# n64cart.net
KiCad netlist of a schematic drawn in EAGLE
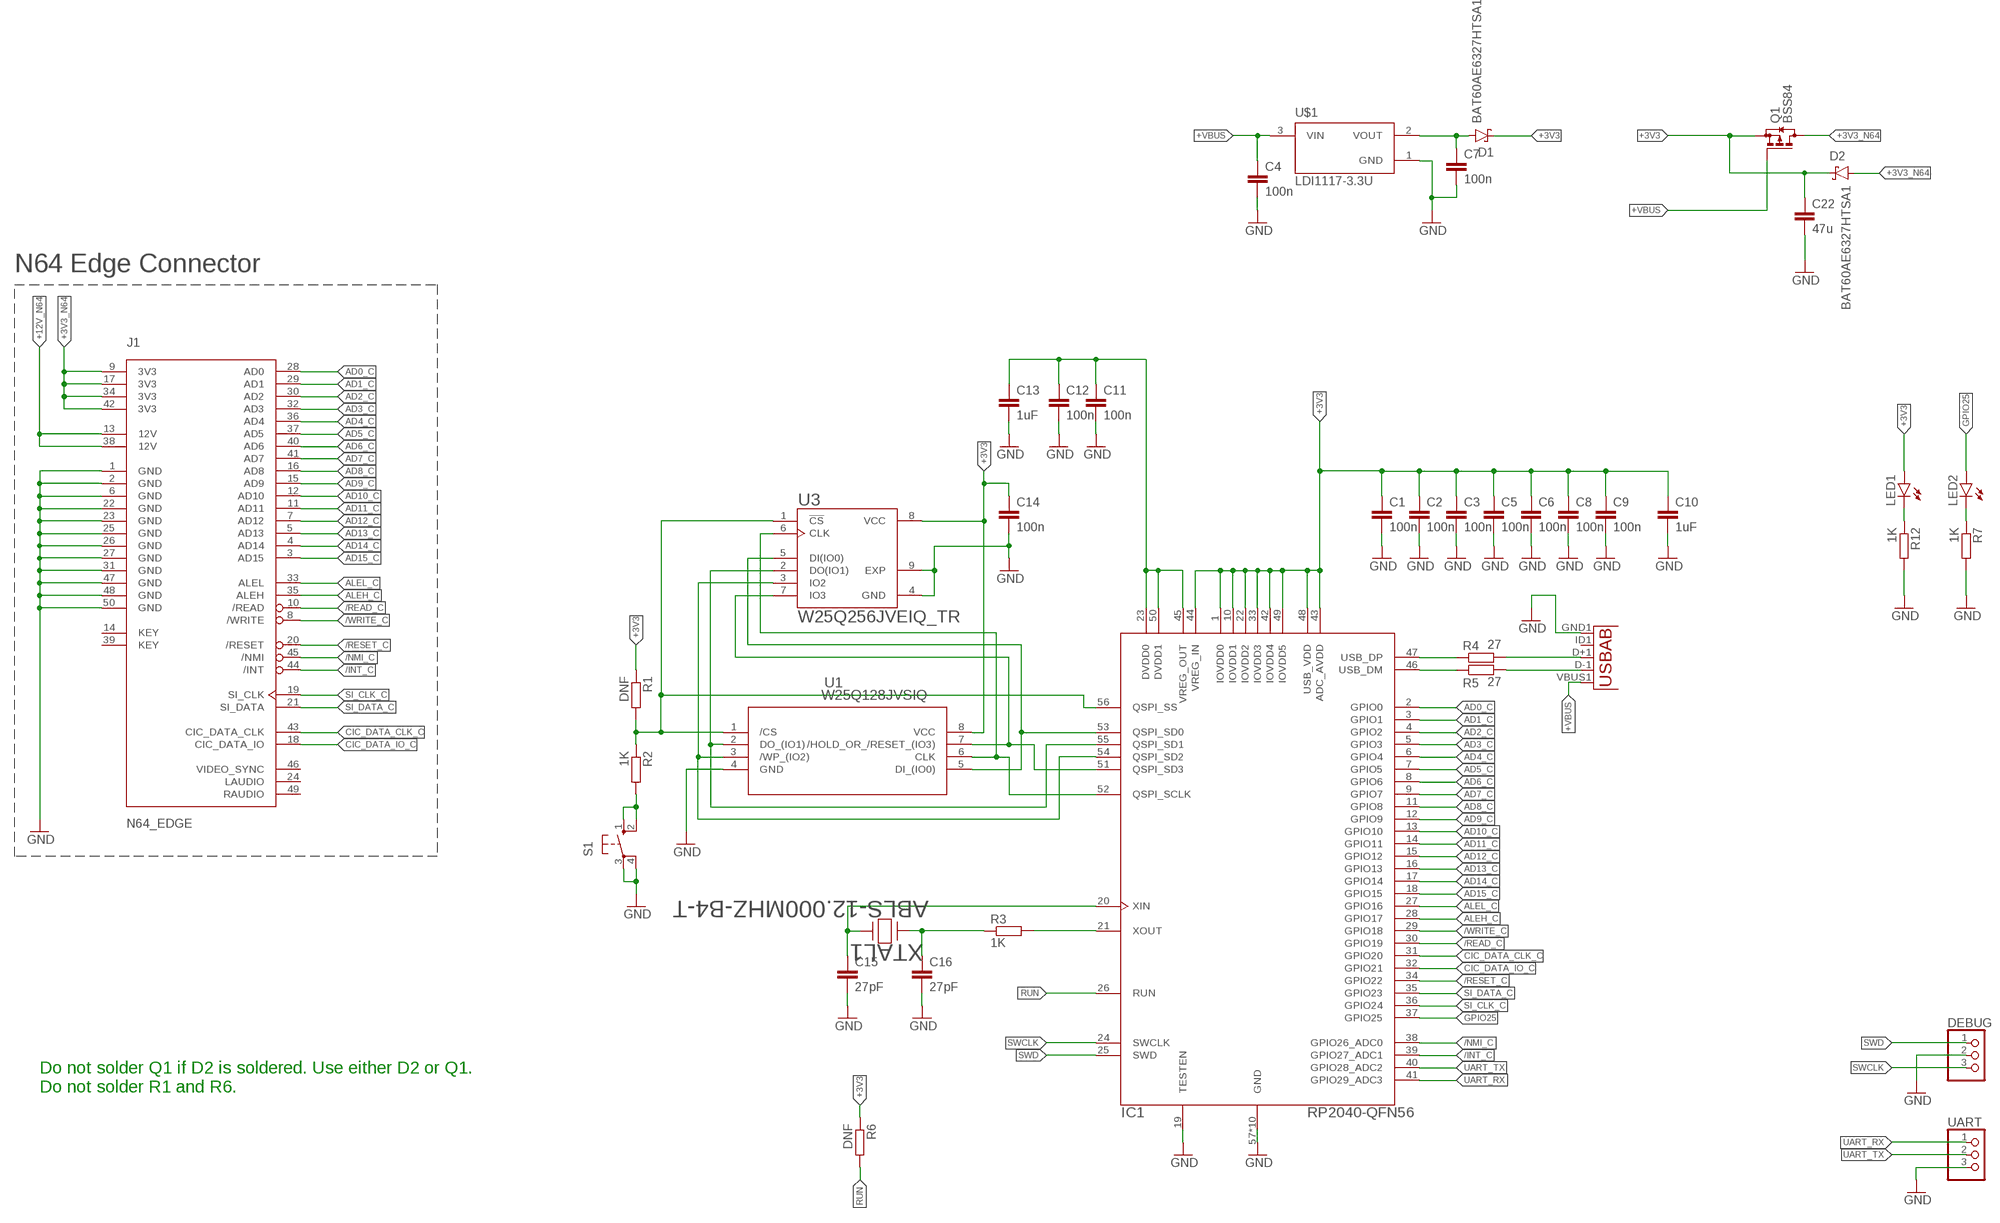
[diagram p0: schematic, sheet 1]

(export (version "E")
  (design (tool "Eeschema 10.0.6"))
  (components
    (comp (ref "C1")
      (value "100n")
      (footprint "eagle-import:C0402")
      (libsource (lib "eagle-import") (part "C-EUC0402"))
    )
    (comp (ref "C2")
      (value "100n")
      (footprint "eagle-import:C0402")
      (libsource (lib "eagle-import") (part "C-EUC0402"))
    )
    (comp (ref "C3")
      (value "100n")
      (footprint "eagle-import:C0402")
      (libsource (lib "eagle-import") (part "C-EUC0402"))
    )
    (comp (ref "C4")
      (value "100n")
      (footprint "eagle-import:C0402")
      (libsource (lib "eagle-import") (part "C-EUC0402"))
    )
    (comp (ref "C5")
      (value "100n")
      (footprint "eagle-import:C0402")
      (libsource (lib "eagle-import") (part "C-EUC0402"))
    )
    (comp (ref "C6")
      (value "100n")
      (footprint "eagle-import:C0402")
      (libsource (lib "eagle-import") (part "C-EUC0402"))
    )
    (comp (ref "C7")
      (value "100n")
      (footprint "eagle-import:C0402")
      (libsource (lib "eagle-import") (part "C-EUC0402"))
    )
    (comp (ref "C8")
      (value "100n")
      (footprint "eagle-import:C0402")
      (libsource (lib "eagle-import") (part "C-EUC0402"))
    )
    (comp (ref "C9")
      (value "100n")
      (footprint "eagle-import:C0402")
      (libsource (lib "eagle-import") (part "C-EUC0402"))
    )
    (comp (ref "C10")
      (value "1uF")
      (footprint "eagle-import:C0402")
      (libsource (lib "eagle-import") (part "C-EUC0402"))
    )
    (comp (ref "C11")
      (value "100n")
      (footprint "eagle-import:C0402")
      (libsource (lib "eagle-import") (part "C-EUC0402"))
    )
    (comp (ref "C12")
      (value "100n")
      (footprint "eagle-import:C0402")
      (libsource (lib "eagle-import") (part "C-EUC0402"))
    )
    (comp (ref "C13")
      (value "1uF")
      (footprint "eagle-import:C0402")
      (libsource (lib "eagle-import") (part "C-EUC0402"))
    )
    (comp (ref "C14")
      (value "100n")
      (footprint "eagle-import:C0402")
      (libsource (lib "eagle-import") (part "C-EUC0402"))
    )
    (comp (ref "C15")
      (value "27pF")
      (footprint "eagle-import:C0402")
      (libsource (lib "eagle-import") (part "C-EUC0402"))
    )
    (comp (ref "C16")
      (value "27pF")
      (footprint "eagle-import:C0402")
      (libsource (lib "eagle-import") (part "C-EUC0402"))
    )
    (comp (ref "C22")
      (value "47u")
      (footprint "eagle-import:C0805")
      (libsource (lib "eagle-import") (part "C-EUC0805"))
    )
    (comp (ref "D1")
      (value "BAT60AE6327HTSA1")
      (footprint "eagle-import:SOD323_ST")
      (libsource (lib "eagle-import") (part "BAT60J"))
    )
    (comp (ref "D2")
      (value "BAT60AE6327HTSA1")
      (footprint "eagle-import:SOD323_ST")
      (libsource (lib "eagle-import") (part "BAT60J"))
    )
    (comp (ref "DEBUG")
      (value "PINHD-1X3")
      (footprint "eagle-import:1X03")
      (libsource (lib "eagle-import") (part "PINHD-1X3"))
    )
    (comp (ref "IC1")
      (value "RP2040-QFN56")
      (footprint "eagle-import:RP2040-QFN-56")
      (libsource (lib "eagle-import") (part "RP2040-QFN56"))
    )
    (comp (ref "J1")
      (value "N64_EDGE")
      (footprint "eagle-import:N64_EDGE")
      (libsource (lib "eagle-import") (part "N64_EDGE"))
    )
    (comp (ref "LED1")
      (value "LED5MM")
      (footprint "eagle-import:LED5MM")
      (libsource (lib "eagle-import") (part "LED5MM"))
    )
    (comp (ref "LED2")
      (value "LED5MM")
      (footprint "eagle-import:LED5MM")
      (libsource (lib "eagle-import") (part "LED5MM"))
    )
    (comp (ref "Q1")
      (value "BSS84")
      (footprint "eagle-import:SOT23")
      (libsource (lib "eagle-import") (part "BSS84"))
    )
    (comp (ref "R1")
      (value "DNF")
      (footprint "eagle-import:R0402")
      (libsource (lib "eagle-import") (part "R-EU_R0402"))
    )
    (comp (ref "R2")
      (value "1K")
      (footprint "eagle-import:R0402")
      (libsource (lib "eagle-import") (part "R-EU_R0402"))
    )
    (comp (ref "R3")
      (value "1K")
      (footprint "eagle-import:R0402")
      (libsource (lib "eagle-import") (part "R-EU_R0402"))
    )
    (comp (ref "R4")
      (value "27")
      (footprint "eagle-import:R0402")
      (libsource (lib "eagle-import") (part "R-EU_R0402"))
    )
    (comp (ref "R5")
      (value "27")
      (footprint "eagle-import:R0402")
      (libsource (lib "eagle-import") (part "R-EU_R0402"))
    )
    (comp (ref "R6")
      (value "DNF")
      (footprint "eagle-import:R0402")
      (libsource (lib "eagle-import") (part "R-EU_R0402"))
    )
    (comp (ref "R7")
      (value "1K")
      (footprint "eagle-import:R0402")
      (libsource (lib "eagle-import") (part "R-EU_R0402"))
    )
    (comp (ref "R12")
      (value "1K")
      (footprint "eagle-import:R0402")
      (libsource (lib "eagle-import") (part "R-EU_R0402"))
    )
    (comp (ref "S1")
      (value "10-XX")
      (footprint "eagle-import:B3F-10XX")
      (fields (field (name "MPN") "B3F-1000"))
      (libsource (lib "eagle-import") (part "10-XX"))
    )
    (comp (ref "U$1")
      (value "LDI1117-3.3U")
      (footprint "eagle-import:LDI1117-3.3U")
      (libsource (lib "eagle-import") (part "LDI1117-3.3U"))
    )
    (comp (ref "U1")
      (value "W25Q128JVSIQ")
      (footprint "eagle-import:SOIC_128JVSIQ_WIN")
      (fields (field (name "COPYRIGHT") "Copyright (C) 2022 Ultra Librarian. All rights reserved."))
      (libsource (lib "eagle-import") (part "W25Q128JVSIQ"))
    )
    (comp (ref "U2")
      (value "USB\"\"")
      (footprint "eagle-import:USB-MICRO-SMD")
      (libsource (lib "eagle-import") (part "USB{dblquote}{dblquote}"))
    )
    (comp (ref "U3")
      (value "W25Q256JVEIQ_TR")
      (footprint "eagle-import:SON127P800X600X80-9N")
      (fields
        (field (name "DIGI-KEY_PART_NUMBER") "W25Q256JVEIQTR-ND")
        (field (name "MF") "Winbond")
        (field (name "MP") "W25Q256JVEIQ TR")
      )
      (libsource (lib "eagle-import") (part "W25Q256JVEIQ_TR"))
    )
    (comp (ref "UART")
      (value "PINHD-1X3")
      (footprint "eagle-import:1X03")
      (libsource (lib "eagle-import") (part "PINHD-1X3"))
    )
    (comp (ref "XTAL1")
      (value "ABLS-12.000MHZ-B4-T")
      (footprint "eagle-import:XTAL_ABLS_ABR")
      (fields (field (name "COPYRIGHT") "Copyright (C) 2022 Ultra Librarian. All rights reserved."))
      (libsource (lib "eagle-import") (part "ABLS-12.000MHZ-B4-T"))
    )
  )
  (nets
    (net (code "1") (name "+3V3") (class "Default")
      (node (ref "C1") (pin "1") (pinfunction "1_1") (pintype "passive"))
      (node (ref "C10") (pin "1") (pinfunction "1_1") (pintype "passive"))
      (node (ref "C14") (pin "1") (pinfunction "1_1") (pintype "passive"))
      (node (ref "C2") (pin "1") (pinfunction "1_1") (pintype "passive"))
      (node (ref "C22") (pin "1") (pinfunction "1_1") (pintype "passive"))
      (node (ref "C3") (pin "1") (pinfunction "1_1") (pintype "passive"))
      (node (ref "C5") (pin "1") (pinfunction "1_1") (pintype "passive"))
      (node (ref "C6") (pin "1") (pinfunction "1_1") (pintype "passive"))
      (node (ref "C8") (pin "1") (pinfunction "1_1") (pintype "passive"))
      (node (ref "C9") (pin "1") (pinfunction "1_1") (pintype "passive"))
      (node (ref "D1") (pin "C") (pinfunction "C_C") (pintype "passive"))
      (node (ref "D2") (pin "C") (pinfunction "C_C") (pintype "passive"))
      (node (ref "IC1") (pin "1") (pinfunction "IOVDD0_1") (pintype "power_in"))
      (node (ref "IC1") (pin "10") (pinfunction "IOVDD1_10") (pintype "power_in"))
      (node (ref "IC1") (pin "22") (pinfunction "IOVDD2_22") (pintype "power_in"))
      (node (ref "IC1") (pin "33") (pinfunction "IOVDD3_33") (pintype "power_in"))
      (node (ref "IC1") (pin "42") (pinfunction "IOVDD4_42") (pintype "power_in"))
      (node (ref "IC1") (pin "43") (pinfunction "ADC_AVDD_43") (pintype "power_in"))
      (node (ref "IC1") (pin "44") (pinfunction "VREG_IN_44") (pintype "power_in"))
      (node (ref "IC1") (pin "48") (pinfunction "USB_VDD_48") (pintype "power_in"))
      (node (ref "IC1") (pin "49") (pinfunction "IOVDD5_49") (pintype "power_in"))
      (node (ref "LED1") (pin "A") (pinfunction "A_A") (pintype "passive"))
      (node (ref "Q1") (pin "2") (pinfunction "S_2") (pintype "passive"))
      (node (ref "R1") (pin "1") (pinfunction "1_1") (pintype "passive"))
      (node (ref "R6") (pin "1") (pinfunction "1_1") (pintype "passive"))
      (node (ref "U1") (pin "8") (pinfunction "VCC_8") (pintype "power_in"))
      (node (ref "U3") (pin "8") (pinfunction "VCC_8") (pintype "power_in"))
    )
    (net (code "2") (name "+3V3_N64") (class "Default")
      (node (ref "D2") (pin "A") (pinfunction "A_A") (pintype "passive"))
      (node (ref "J1") (pin "17") (pinfunction "3V3_17") (pintype "power_in"))
      (node (ref "J1") (pin "34") (pinfunction "3V3_34") (pintype "power_in"))
      (node (ref "J1") (pin "42") (pinfunction "3V3_42") (pintype "power_in"))
      (node (ref "J1") (pin "9") (pinfunction "3V3_9") (pintype "power_in"))
      (node (ref "Q1") (pin "3") (pinfunction "D_3") (pintype "passive"))
    )
    (net (code "3") (name "+12V_N64") (class "Default")
      (node (ref "J1") (pin "13") (pinfunction "12V_13") (pintype "power_in"))
      (node (ref "J1") (pin "38") (pinfunction "12V_38") (pintype "power_in"))
    )
    (net (code "4") (name "+VBUS") (class "Default")
      (node (ref "C4") (pin "1") (pinfunction "1_1") (pintype "passive"))
      (node (ref "Q1") (pin "1") (pinfunction "G_1") (pintype "passive"))
      (node (ref "U$1") (pin "3") (pinfunction "VIN_3") (pintype "input"))
      (node (ref "U2") (pin "VBUS1") (pinfunction "VBUS_VBUS1") (pintype "bidirectional"))
    )
    (net (code "5") (name "AD0_C") (class "Default")
      (node (ref "IC1") (pin "2") (pinfunction "GPIO0_2") (pintype "bidirectional"))
      (node (ref "J1") (pin "28") (pinfunction "AD0_28") (pintype "bidirectional"))
    )
    (net (code "6") (name "AD1_C") (class "Default")
      (node (ref "IC1") (pin "3") (pinfunction "GPIO1_3") (pintype "bidirectional"))
      (node (ref "J1") (pin "29") (pinfunction "AD1_29") (pintype "bidirectional"))
    )
    (net (code "7") (name "AD2_C") (class "Default")
      (node (ref "IC1") (pin "4") (pinfunction "GPIO2_4") (pintype "bidirectional"))
      (node (ref "J1") (pin "30") (pinfunction "AD2_30") (pintype "bidirectional"))
    )
    (net (code "8") (name "AD3_C") (class "Default")
      (node (ref "IC1") (pin "5") (pinfunction "GPIO3_5") (pintype "bidirectional"))
      (node (ref "J1") (pin "32") (pinfunction "AD3_32") (pintype "bidirectional"))
    )
    (net (code "9") (name "AD4_C") (class "Default")
      (node (ref "IC1") (pin "6") (pinfunction "GPIO4_6") (pintype "bidirectional"))
      (node (ref "J1") (pin "36") (pinfunction "AD4_36") (pintype "bidirectional"))
    )
    (net (code "10") (name "AD5_C") (class "Default")
      (node (ref "IC1") (pin "7") (pinfunction "GPIO5_7") (pintype "bidirectional"))
      (node (ref "J1") (pin "37") (pinfunction "AD5_37") (pintype "bidirectional"))
    )
    (net (code "11") (name "AD6_C") (class "Default")
      (node (ref "IC1") (pin "8") (pinfunction "GPIO6_8") (pintype "bidirectional"))
      (node (ref "J1") (pin "40") (pinfunction "AD6_40") (pintype "bidirectional"))
    )
    (net (code "12") (name "AD7_C") (class "Default")
      (node (ref "IC1") (pin "9") (pinfunction "GPIO7_9") (pintype "bidirectional"))
      (node (ref "J1") (pin "41") (pinfunction "AD7_41") (pintype "bidirectional"))
    )
    (net (code "13") (name "AD8_C") (class "Default")
      (node (ref "IC1") (pin "11") (pinfunction "GPIO8_11") (pintype "bidirectional"))
      (node (ref "J1") (pin "16") (pinfunction "AD8_16") (pintype "bidirectional"))
    )
    (net (code "14") (name "AD9_C") (class "Default")
      (node (ref "IC1") (pin "12") (pinfunction "GPIO9_12") (pintype "bidirectional"))
      (node (ref "J1") (pin "15") (pinfunction "AD9_15") (pintype "bidirectional"))
    )
    (net (code "15") (name "AD10_C") (class "Default")
      (node (ref "IC1") (pin "13") (pinfunction "GPIO10_13") (pintype "bidirectional"))
      (node (ref "J1") (pin "12") (pinfunction "AD10_12") (pintype "bidirectional"))
    )
    (net (code "16") (name "AD11_C") (class "Default")
      (node (ref "IC1") (pin "14") (pinfunction "GPIO11_14") (pintype "bidirectional"))
      (node (ref "J1") (pin "11") (pinfunction "AD11_11") (pintype "bidirectional"))
    )
    (net (code "17") (name "AD12_C") (class "Default")
      (node (ref "IC1") (pin "15") (pinfunction "GPIO12_15") (pintype "bidirectional"))
      (node (ref "J1") (pin "7") (pinfunction "AD12_7") (pintype "bidirectional"))
    )
    (net (code "18") (name "AD13_C") (class "Default")
      (node (ref "IC1") (pin "16") (pinfunction "GPIO13_16") (pintype "bidirectional"))
      (node (ref "J1") (pin "5") (pinfunction "AD13_5") (pintype "bidirectional"))
    )
    (net (code "19") (name "AD14_C") (class "Default")
      (node (ref "IC1") (pin "17") (pinfunction "GPIO14_17") (pintype "bidirectional"))
      (node (ref "J1") (pin "4") (pinfunction "AD14_4") (pintype "bidirectional"))
    )
    (net (code "20") (name "AD15_C") (class "Default")
      (node (ref "IC1") (pin "18") (pinfunction "GPIO15_18") (pintype "bidirectional"))
      (node (ref "J1") (pin "3") (pinfunction "AD15_3") (pintype "bidirectional"))
    )
    (net (code "21") (name "ALEH_C") (class "Default")
      (node (ref "IC1") (pin "28") (pinfunction "GPIO17_28") (pintype "bidirectional"))
      (node (ref "J1") (pin "35") (pinfunction "ALEH_35") (pintype "output"))
    )
    (net (code "22") (name "ALEL_C") (class "Default")
      (node (ref "IC1") (pin "27") (pinfunction "GPIO16_27") (pintype "bidirectional"))
      (node (ref "J1") (pin "33") (pinfunction "ALEL_33") (pintype "output"))
    )
    (net (code "23") (name "CIC_DATA_CLK_C") (class "Default")
      (node (ref "IC1") (pin "31") (pinfunction "GPIO20_31") (pintype "bidirectional"))
      (node (ref "J1") (pin "43") (pinfunction "CIC_DATA_CLK_43") (pintype "output"))
    )
    (net (code "24") (name "CIC_DATA_IO_C") (class "Default")
      (node (ref "IC1") (pin "32") (pinfunction "GPIO21_32") (pintype "bidirectional"))
      (node (ref "J1") (pin "18") (pinfunction "CIC_DATA_IO_18") (pintype "bidirectional"))
    )
    (net (code "25") (name "GND") (class "Default")
      (node (ref "C1") (pin "2") (pinfunction "2_2") (pintype "passive"))
      (node (ref "C10") (pin "2") (pinfunction "2_2") (pintype "passive"))
      (node (ref "C11") (pin "2") (pinfunction "2_2") (pintype "passive"))
      (node (ref "C12") (pin "2") (pinfunction "2_2") (pintype "passive"))
      (node (ref "C13") (pin "2") (pinfunction "2_2") (pintype "passive"))
      (node (ref "C14") (pin "2") (pinfunction "2_2") (pintype "passive"))
      (node (ref "C15") (pin "2") (pinfunction "2_2") (pintype "passive"))
      (node (ref "C16") (pin "2") (pinfunction "2_2") (pintype "passive"))
      (node (ref "C2") (pin "2") (pinfunction "2_2") (pintype "passive"))
      (node (ref "C22") (pin "2") (pinfunction "2_2") (pintype "passive"))
      (node (ref "C3") (pin "2") (pinfunction "2_2") (pintype "passive"))
      (node (ref "C4") (pin "2") (pinfunction "2_2") (pintype "passive"))
      (node (ref "C5") (pin "2") (pinfunction "2_2") (pintype "passive"))
      (node (ref "C6") (pin "2") (pinfunction "2_2") (pintype "passive"))
      (node (ref "C7") (pin "2") (pinfunction "2_2") (pintype "passive"))
      (node (ref "C8") (pin "2") (pinfunction "2_2") (pintype "passive"))
      (node (ref "C9") (pin "2") (pinfunction "2_2") (pintype "passive"))
      (node (ref "DEBUG") (pin "2") (pinfunction "2_2") (pintype "passive"))
      (node (ref "IC1") (pin "19") (pinfunction "TESTEN_19") (pintype "passive"))
      (node (ref "IC1") (pin "57") (pinfunction "GND_57") (pintype "power_in"))
      (node (ref "IC1") (pin "58") (pinfunction "GND_58") (pintype "power_in"))
      (node (ref "IC1") (pin "59") (pinfunction "GND_59") (pintype "power_in"))
      (node (ref "IC1") (pin "60") (pinfunction "GND_60") (pintype "power_in"))
      (node (ref "IC1") (pin "61") (pinfunction "GND_61") (pintype "power_in"))
      (node (ref "IC1") (pin "62") (pinfunction "GND_62") (pintype "power_in"))
      (node (ref "IC1") (pin "63") (pinfunction "GND_63") (pintype "power_in"))
      (node (ref "IC1") (pin "64") (pinfunction "GND_64") (pintype "power_in"))
      (node (ref "IC1") (pin "65") (pinfunction "GND_65") (pintype "power_in"))
      (node (ref "IC1") (pin "66") (pinfunction "GND_66") (pintype "power_in"))
      (node (ref "J1") (pin "1") (pinfunction "GND_1") (pintype "power_in"))
      (node (ref "J1") (pin "2") (pinfunction "GND_2") (pintype "power_in"))
      (node (ref "J1") (pin "22") (pinfunction "GND_22") (pintype "power_in"))
      (node (ref "J1") (pin "23") (pinfunction "GND_23") (pintype "power_in"))
      (node (ref "J1") (pin "25") (pinfunction "GND_25") (pintype "power_in"))
      (node (ref "J1") (pin "26") (pinfunction "GND_26") (pintype "power_in"))
      (node (ref "J1") (pin "27") (pinfunction "GND_27") (pintype "power_in"))
      (node (ref "J1") (pin "31") (pinfunction "GND_31") (pintype "power_in"))
      (node (ref "J1") (pin "47") (pinfunction "GND_47") (pintype "power_in"))
      (node (ref "J1") (pin "48") (pinfunction "GND_48") (pintype "power_in"))
      (node (ref "J1") (pin "50") (pinfunction "GND_50") (pintype "power_in"))
      (node (ref "J1") (pin "6") (pinfunction "GND_6") (pintype "power_in"))
      (node (ref "R12") (pin "2") (pinfunction "2_2") (pintype "passive"))
      (node (ref "R7") (pin "2") (pinfunction "2_2") (pintype "passive"))
      (node (ref "S1") (pin "3") (pinfunction "P_3") (pintype "passive"))
      (node (ref "S1") (pin "4") (pinfunction "P1_4") (pintype "passive"))
      (node (ref "U$1") (pin "1") (pinfunction "GND_1") (pintype "power_in"))
      (node (ref "U1") (pin "4") (pinfunction "GND_4") (pintype "passive"))
      (node (ref "U2") (pin "GND1") (pinfunction "GND_GND1") (pintype "bidirectional"))
      (node (ref "U3") (pin "4") (pinfunction "GND_4") (pintype "power_in"))
      (node (ref "U3") (pin "9") (pinfunction "EXP_9") (pintype "power_in"))
      (node (ref "UART") (pin "3") (pinfunction "3_3") (pintype "passive"))
    )
    (net (code "26") (name "GPIO25") (class "Default")
      (node (ref "IC1") (pin "37") (pinfunction "GPIO25_37") (pintype "bidirectional"))
      (node (ref "LED2") (pin "A") (pinfunction "A_A") (pintype "passive"))
    )
    (net (code "27") (name "Net-(C16-Pad1)") (class "Default")
      (node (ref "C16") (pin "1") (pinfunction "1_1") (pintype "passive"))
      (node (ref "R3") (pin "1") (pinfunction "1_1") (pintype "passive"))
      (node (ref "XTAL1") (pin "1") (pinfunction "1_1") (pintype "passive"))
    )
    (net (code "28") (name "Net-(IC1-DVDD0)") (class "Default")
      (node (ref "C11") (pin "1") (pinfunction "1_1") (pintype "passive"))
      (node (ref "C12") (pin "1") (pinfunction "1_1") (pintype "passive"))
      (node (ref "C13") (pin "1") (pinfunction "1_1") (pintype "passive"))
      (node (ref "IC1") (pin "23") (pinfunction "DVDD0_23") (pintype "power_in"))
      (node (ref "IC1") (pin "45") (pinfunction "VREG_OUT_45") (pintype "power_in"))
      (node (ref "IC1") (pin "50") (pinfunction "DVDD1_50") (pintype "power_in"))
    )
    (net (code "29") (name "Net-(IC1-QSPI_SCLK)") (class "Default")
      (node (ref "IC1") (pin "52") (pinfunction "QSPI_SCLK_52") (pintype "output"))
      (node (ref "U1") (pin "6") (pinfunction "CLK_6") (pintype "passive"))
      (node (ref "U3") (pin "6") (pinfunction "CLK_6") (pintype "input"))
    )
    (net (code "30") (name "Net-(IC1-QSPI_SD0)") (class "Default")
      (node (ref "IC1") (pin "53") (pinfunction "QSPI_SD0_53") (pintype "bidirectional"))
      (node (ref "U1") (pin "5") (pinfunction "DI_(IO0)_5") (pintype "passive"))
      (node (ref "U3") (pin "5") (pinfunction "DI(IO0)_5") (pintype "bidirectional"))
    )
    (net (code "31") (name "Net-(IC1-QSPI_SD1)") (class "Default")
      (node (ref "IC1") (pin "55") (pinfunction "QSPI_SD1_55") (pintype "bidirectional"))
      (node (ref "U1") (pin "2") (pinfunction "DO_(IO1)_2") (pintype "passive"))
      (node (ref "U3") (pin "2") (pinfunction "DO(IO1)_2") (pintype "bidirectional"))
    )
    (net (code "32") (name "Net-(IC1-QSPI_SD2)") (class "Default")
      (node (ref "IC1") (pin "54") (pinfunction "QSPI_SD2_54") (pintype "bidirectional"))
      (node (ref "U1") (pin "3") (pinfunction "/WP_(IO2)_3") (pintype "passive"))
      (node (ref "U3") (pin "3") (pinfunction "IO2_3") (pintype "bidirectional"))
    )
    (net (code "33") (name "Net-(IC1-QSPI_SD3)") (class "Default")
      (node (ref "IC1") (pin "51") (pinfunction "QSPI_SD3_51") (pintype "bidirectional"))
      (node (ref "U1") (pin "7") (pinfunction "/HOLD_OR_/RESET_(IO3)_7") (pintype "passive"))
      (node (ref "U3") (pin "7") (pinfunction "IO3_7") (pintype "bidirectional"))
    )
    (net (code "34") (name "Net-(IC1-QSPI_SS)") (class "Default")
      (node (ref "IC1") (pin "56") (pinfunction "QSPI_SS_56") (pintype "bidirectional"))
      (node (ref "R1") (pin "2") (pinfunction "2_2") (pintype "passive"))
      (node (ref "R2") (pin "1") (pinfunction "1_1") (pintype "passive"))
      (node (ref "U1") (pin "1") (pinfunction "/CS_1") (pintype "passive"))
      (node (ref "U3") (pin "1") (pinfunction "~{CS}_1") (pintype "input"))
    )
    (net (code "35") (name "Net-(IC1-USB_DM)") (class "Default")
      (node (ref "IC1") (pin "46") (pinfunction "USB_DM_46") (pintype "bidirectional"))
      (node (ref "R5") (pin "1") (pinfunction "1_1") (pintype "passive"))
    )
    (net (code "36") (name "Net-(IC1-USB_DP)") (class "Default")
      (node (ref "IC1") (pin "47") (pinfunction "USB_DP_47") (pintype "bidirectional"))
      (node (ref "R4") (pin "1") (pinfunction "1_1") (pintype "passive"))
    )
    (net (code "37") (name "Net-(IC1-XIN)") (class "Default")
      (node (ref "C15") (pin "1") (pinfunction "1_1") (pintype "passive"))
      (node (ref "IC1") (pin "20") (pinfunction "XIN_20") (pintype "input"))
      (node (ref "XTAL1") (pin "2") (pinfunction "2_2") (pintype "passive"))
    )
    (net (code "38") (name "Net-(IC1-XOUT)") (class "Default")
      (node (ref "IC1") (pin "21") (pinfunction "XOUT_21") (pintype "passive"))
      (node (ref "R3") (pin "2") (pinfunction "2_2") (pintype "passive"))
    )
    (net (code "39") (name "Net-(LED1-C)") (class "Default")
      (node (ref "LED1") (pin "K") (pinfunction "C_K") (pintype "passive"))
      (node (ref "R12") (pin "1") (pinfunction "1_1") (pintype "passive"))
    )
    (net (code "40") (name "Net-(LED2-C)") (class "Default")
      (node (ref "LED2") (pin "K") (pinfunction "C_K") (pintype "passive"))
      (node (ref "R7") (pin "1") (pinfunction "1_1") (pintype "passive"))
    )
    (net (code "41") (name "Net-(S1-S)") (class "Default")
      (node (ref "R2") (pin "2") (pinfunction "2_2") (pintype "passive"))
      (node (ref "S1") (pin "1") (pinfunction "S_1") (pintype "passive"))
      (node (ref "S1") (pin "2") (pinfunction "S1_2") (pintype "passive"))
    )
    (net (code "42") (name "Net-(U$1-VOUT)") (class "Default")
      (node (ref "C7") (pin "1") (pinfunction "1_1") (pintype "passive"))
      (node (ref "D1") (pin "A") (pinfunction "A_A") (pintype "passive"))
      (node (ref "U$1") (pin "2") (pinfunction "VOUT_2") (pintype "output"))
    )
    (net (code "43") (name "Net-(U2-D+)") (class "Default")
      (node (ref "R4") (pin "2") (pinfunction "2_2") (pintype "passive"))
      (node (ref "U2") (pin "D+1") (pinfunction "D+_D+1") (pintype "bidirectional"))
    )
    (net (code "44") (name "Net-(U2-D-)") (class "Default")
      (node (ref "R5") (pin "2") (pinfunction "2_2") (pintype "passive"))
      (node (ref "U2") (pin "D-1") (pinfunction "D-_D-1") (pintype "bidirectional"))
    )
    (net (code "45") (name "RUN") (class "Default")
      (node (ref "IC1") (pin "26") (pinfunction "RUN_26") (pintype "input"))
      (node (ref "R6") (pin "2") (pinfunction "2_2") (pintype "passive"))
    )
    (net (code "46") (name "SI_CLK_C") (class "Default")
      (node (ref "IC1") (pin "36") (pinfunction "GPIO24_36") (pintype "bidirectional"))
      (node (ref "J1") (pin "19") (pinfunction "SI_CLK_19") (pintype "output"))
    )
    (net (code "47") (name "SI_DATA_C") (class "Default")
      (node (ref "IC1") (pin "35") (pinfunction "GPIO23_35") (pintype "bidirectional"))
      (node (ref "J1") (pin "21") (pinfunction "SI_DATA_21") (pintype "bidirectional"))
    )
    (net (code "48") (name "SWCLK") (class "Default")
      (node (ref "DEBUG") (pin "3") (pinfunction "3_3") (pintype "passive"))
      (node (ref "IC1") (pin "24") (pinfunction "SWCLK_24") (pintype "output"))
    )
    (net (code "49") (name "SWD") (class "Default")
      (node (ref "DEBUG") (pin "1") (pinfunction "1_1") (pintype "passive"))
      (node (ref "IC1") (pin "25") (pinfunction "SWD_25") (pintype "bidirectional"))
    )
    (net (code "50") (name "UART_RX") (class "Default")
      (node (ref "IC1") (pin "41") (pinfunction "GPIO29_ADC3_41") (pintype "bidirectional"))
      (node (ref "UART") (pin "1") (pinfunction "1_1") (pintype "passive"))
    )
    (net (code "51") (name "UART_TX") (class "Default")
      (node (ref "IC1") (pin "40") (pinfunction "GPIO28_ADC2_40") (pintype "bidirectional"))
      (node (ref "UART") (pin "2") (pinfunction "2_2") (pintype "passive"))
    )
    (net (code "52") (name "unconnected-(J1-KEY-Pad14)") (class "Default")
      (node (ref "J1") (pin "14") (pinfunction "KEY_14") (pintype "no_connect"))
    )
    (net (code "53") (name "unconnected-(J1-KEY-Pad39)") (class "Default")
      (node (ref "J1") (pin "39") (pinfunction "KEY_39") (pintype "no_connect"))
    )
    (net (code "54") (name "unconnected-(J1-LAUDIO-Pad24)") (class "Default")
      (node (ref "J1") (pin "24") (pinfunction "LAUDIO_24") (pintype "input"))
    )
    (net (code "55") (name "unconnected-(J1-RAUDIO-Pad49)") (class "Default")
      (node (ref "J1") (pin "49") (pinfunction "RAUDIO_49") (pintype "input"))
    )
    (net (code "56") (name "unconnected-(J1-VIDEO_SYNC-Pad46)") (class "Default")
      (node (ref "J1") (pin "46") (pinfunction "VIDEO_SYNC_46") (pintype "output"))
    )
    (net (code "57") (name "unconnected-(U2-USBID-PadID1)") (class "Default")
      (node (ref "U2") (pin "ID1") (pinfunction "USBID_ID1") (pintype "bidirectional"))
    )
    (net (code "58") (name "{slash}INT_C") (class "Default")
      (node (ref "IC1") (pin "39") (pinfunction "GPIO27_ADC1_39") (pintype "bidirectional"))
      (node (ref "J1") (pin "44") (pinfunction "/INT_44") (pintype "input"))
    )
    (net (code "59") (name "{slash}NMI_C") (class "Default")
      (node (ref "IC1") (pin "38") (pinfunction "GPIO26_ADC0_38") (pintype "bidirectional"))
      (node (ref "J1") (pin "45") (pinfunction "/NMI_45") (pintype "output"))
    )
    (net (code "60") (name "{slash}READ_C") (class "Default")
      (node (ref "IC1") (pin "30") (pinfunction "GPIO19_30") (pintype "bidirectional"))
      (node (ref "J1") (pin "10") (pinfunction "/READ_10") (pintype "output"))
    )
    (net (code "61") (name "{slash}RESET_C") (class "Default")
      (node (ref "IC1") (pin "34") (pinfunction "GPIO22_34") (pintype "bidirectional"))
      (node (ref "J1") (pin "20") (pinfunction "/RESET_20") (pintype "output"))
    )
    (net (code "62") (name "{slash}WRITE_C") (class "Default")
      (node (ref "IC1") (pin "29") (pinfunction "GPIO18_29") (pintype "bidirectional"))
      (node (ref "J1") (pin "8") (pinfunction "/WRITE_8") (pintype "output"))
    )
  )
)
